# ee207_week_2_lab.net
KiCad netlist of a schematic drawn in Altium Designer
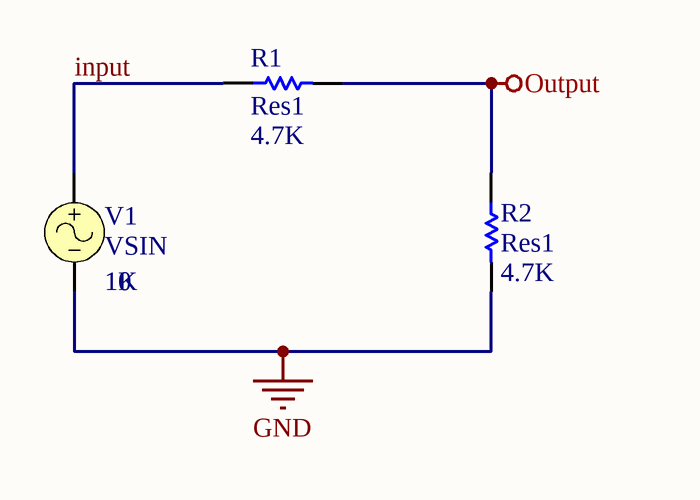
[diagram p0: ee207 week 2 lab.SchDoc]

(export (version "E")
  (design (tool "Eeschema 10.0.6"))
  (components
    (comp (ref "R1")
      (value "Res1")
      (footprint "AXIAL-0.3")
      (description "Resistor")
      (fields (field (name "ALTIUM_VALUE") "4.7K") (field (name "PUBLISHER") "Altium Limited"))
      (libsource (lib "Miscellaneous Devices") (part "Res1"))
    )
    (comp (ref "R2")
      (value "Res1")
      (footprint "AXIAL-0.3")
      (description "Resistor")
      (fields (field (name "ALTIUM_VALUE") "4.7K") (field (name "PUBLISHER") "Altium Limited"))
      (libsource (lib "Miscellaneous Devices") (part "Res1"))
    )
    (comp (ref "V1")
      (value "VSIN")
      (description "Sinusoidal Voltage Source")
      (fields
        (field (name "AMPLITUDE") "10")
        (field (name "FREQUENCY") "1K")
        (field (name "PUBLISHER") "Altium Limited")
      )
      (libsource (lib "Simulation Sources") (part "VSIN"))
    )
  )
  (nets
    (net (code "1") (name "/input") (class "Default")
      (node (ref "R1") (pin "1") (pinfunction "1_1") (pintype "passive"))
      (node (ref "V1") (pin "1") (pinfunction "1_1") (pintype "passive"))
    )
    (net (code "2") (name "GND") (class "Default")
      (node (ref "R2") (pin "2") (pinfunction "2_2") (pintype "passive"))
      (node (ref "V1") (pin "2") (pinfunction "2_2") (pintype "passive"))
    )
    (net (code "3") (name "Output") (class "Default")
      (node (ref "R1") (pin "2") (pinfunction "2_2") (pintype "passive"))
      (node (ref "R2") (pin "1") (pinfunction "1_1") (pintype "passive"))
    )
  )
)
